# Power_Generation_-_Connector.net
KiCad netlist of a schematic drawn in Altium Designer
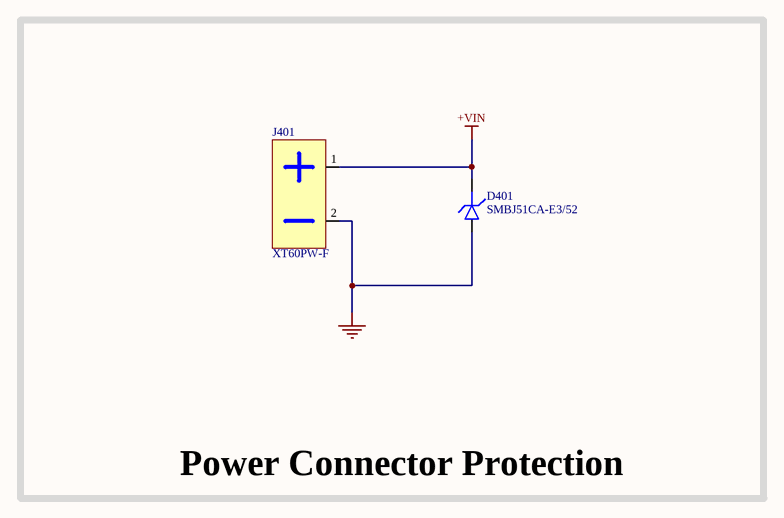
[diagram p0: Power Generation - Connector.SchDoc]

(export (version "E")
  (design (tool "Eeschema 10.0.6"))
  (components
    (comp (ref "D401")
      (value "SMBJ51CA-E3/52")
      (description "D_SMB_TVS")
      (libsource (lib "Schematic-Lib-PhilsLab") (part "D_SMB_TVS"))
    )
    (comp (ref "J401")
      (value "XT60PW-F")
      (footprint "XT60PW-F")
      (description "XT60 horizontal female 2-pin AMASS")
      (fields (field (name "MANUFACTURER") "AMASS"))
      (libsource (lib "Schematic-Lib-PhilsLab") (part "XT60PW-F"))
    )
  )
  (nets
    (net (code "1") (name "+VIN") (class "Default")
      (node (ref "D401") (pin "1") (pinfunction "K_1") (pintype "passive"))
      (node (ref "J401") (pin "1") (pinfunction "V+_1") (pintype "power_in"))
    )
    (net (code "2") (name "GND") (class "Default")
      (node (ref "D401") (pin "2") (pinfunction "A_2") (pintype "passive"))
      (node (ref "J401") (pin "2") (pinfunction "V-_2") (pintype "power_in"))
    )
  )
)
